# 3_Latch-Connector_Stage.net
KiCad netlist of a schematic drawn in Altium Designer
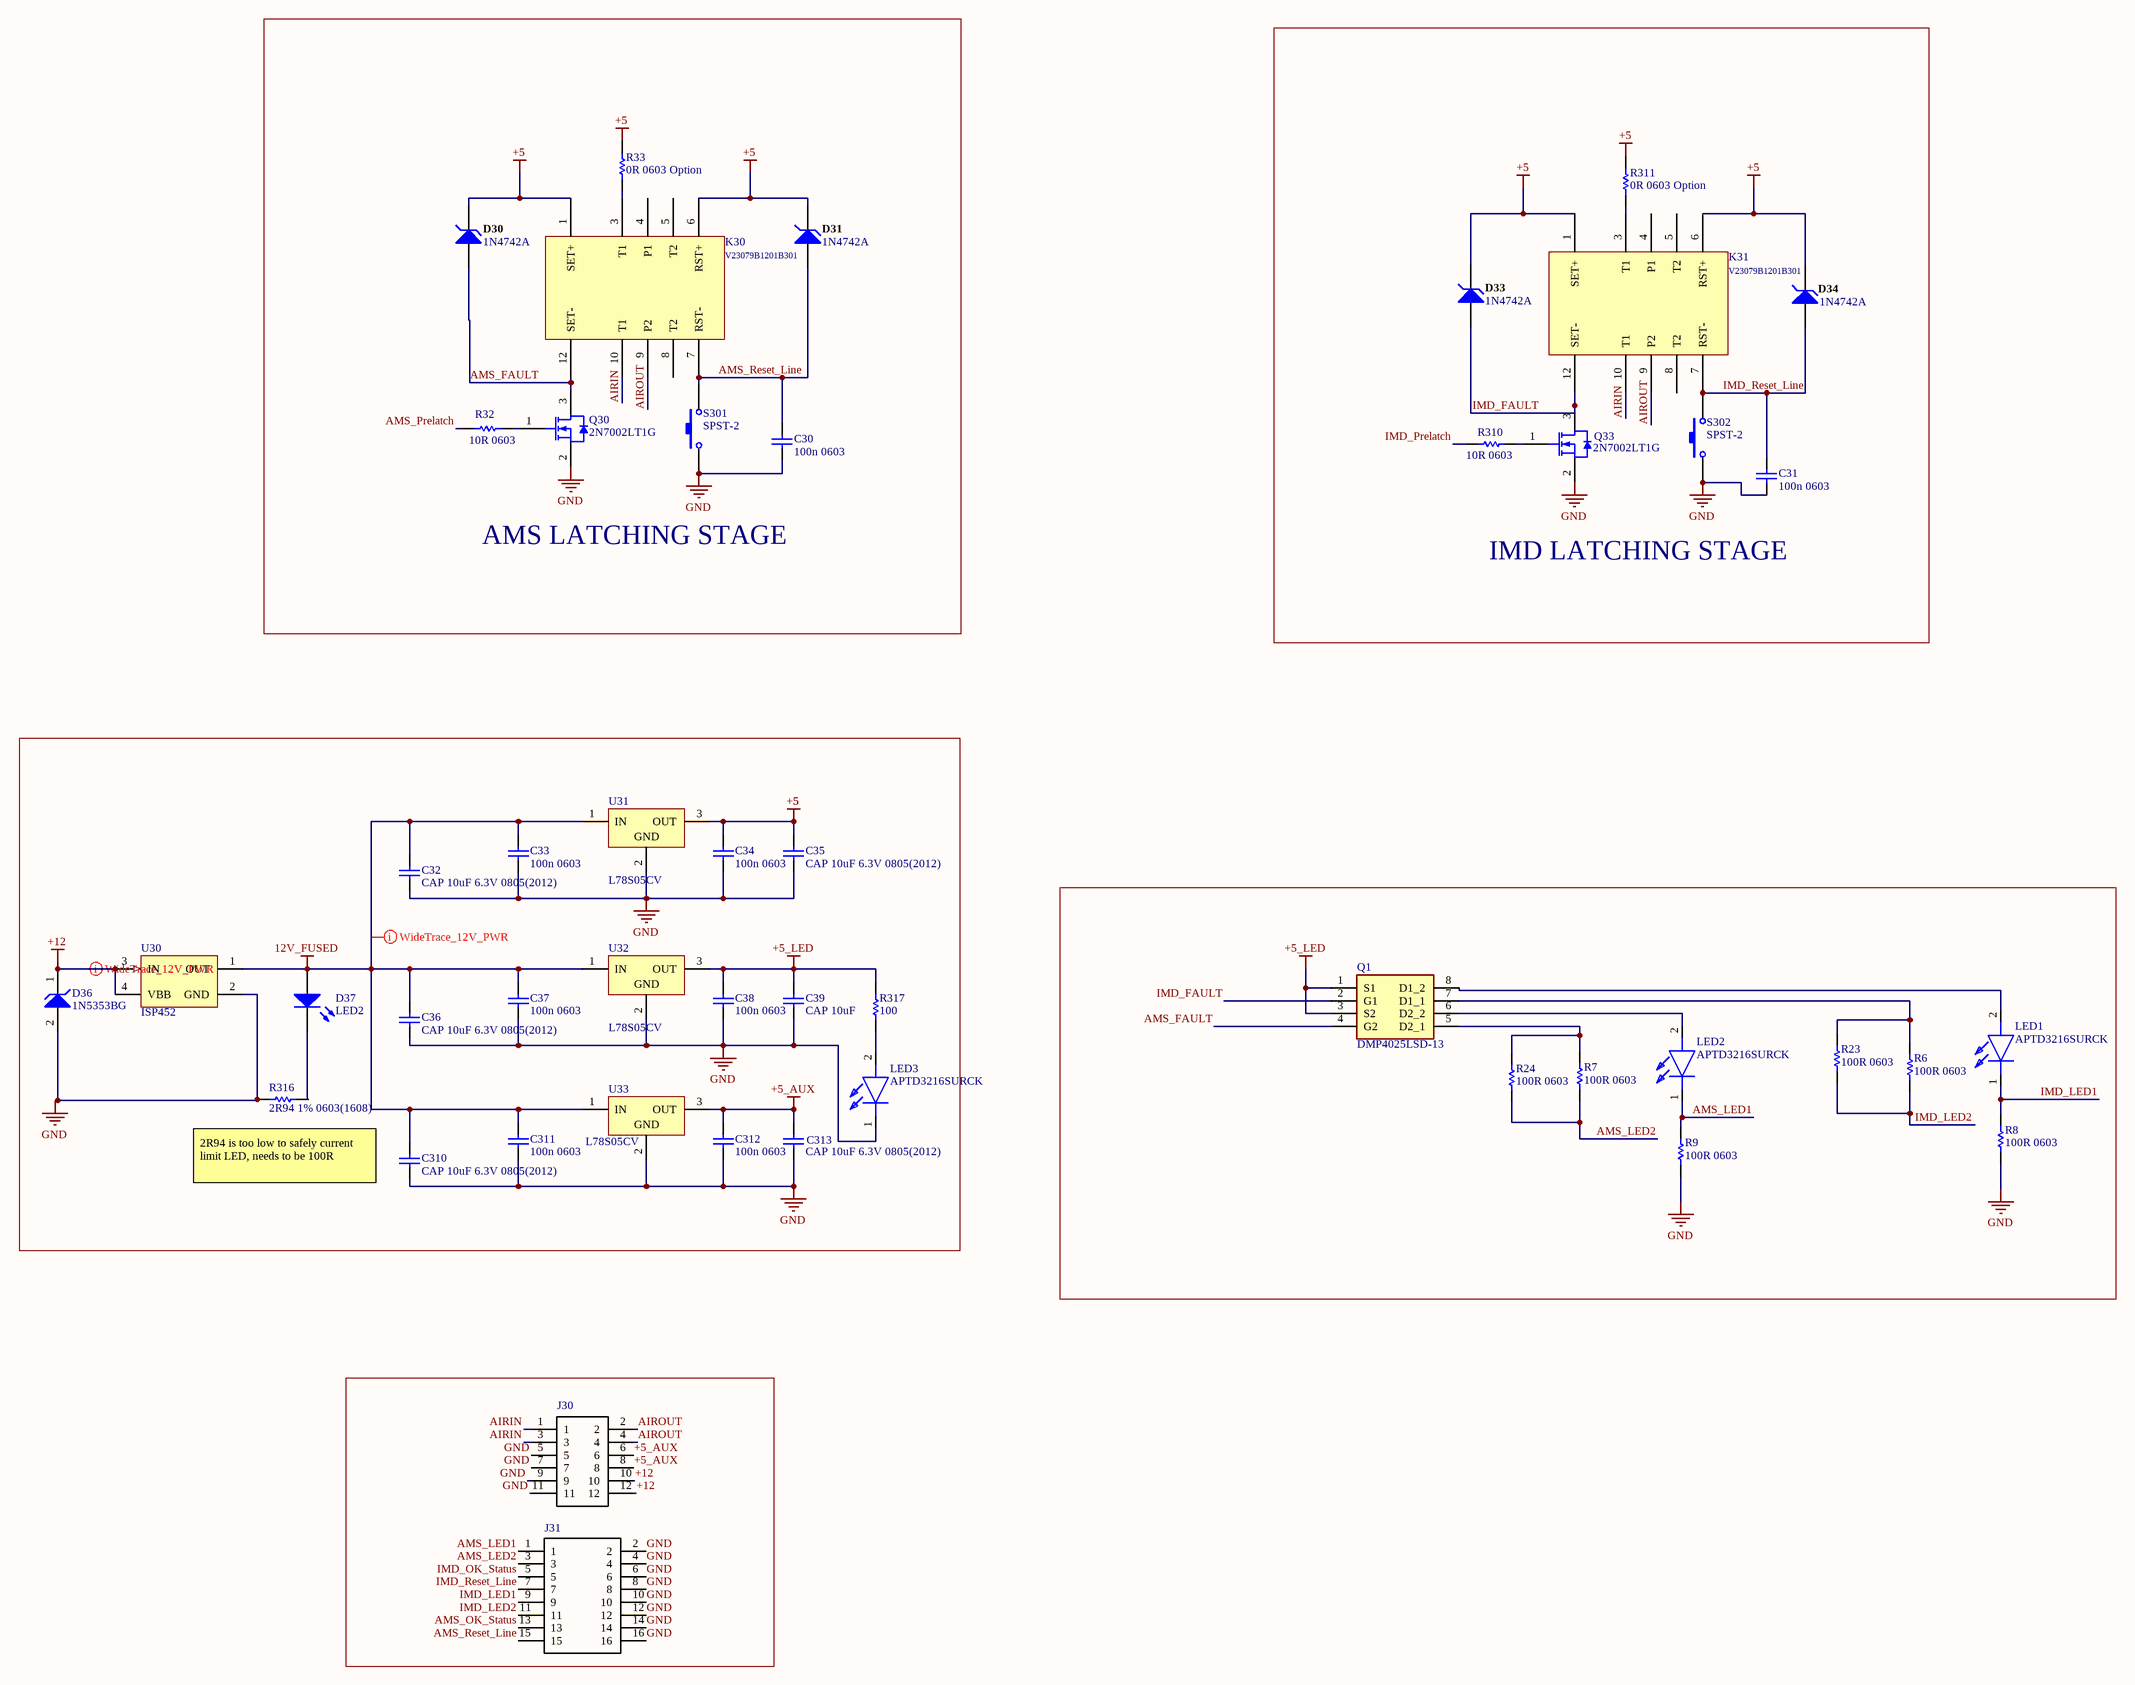
[diagram p0: [3] Latch-Connector_Stage.SchDoc]

(export (version "E")
  (design (tool "Eeschema 10.0.6"))
  (components
    (comp (ref "C30")
      (value "100n 0603")
      (footprint "CAPC0603(1608)100_M")
      (libsource (lib "CAP100n") (part "CAP"))
    )
    (comp (ref "C31")
      (value "100n 0603")
      (footprint "CAPC0603(1608)100_M")
      (libsource (lib "CAP100n") (part "CAP"))
    )
    (comp (ref "C32")
      (value "CAP 10uF 6.3V 0805(2012)")
      (footprint "CAPC0805(2012)145_L")
      (description "CAP 10uF 6.3V ±10% 0805 (2012 Metric) Thickness 1.45mm SMD")
      (fields (field (name "TOLERANCE") "Â±10%"))
      (libsource (lib "Altium Content Vault") (part "CAP"))
    )
    (comp (ref "C33")
      (value "100n 0603")
      (footprint "CAPC0603(1608)100_M")
      (libsource (lib "CAP100n") (part "CAP"))
    )
    (comp (ref "C34")
      (value "100n 0603")
      (footprint "CAPC0603(1608)100_M")
      (libsource (lib "CAP100n") (part "CAP"))
    )
    (comp (ref "C35")
      (value "CAP 10uF 6.3V 0805(2012)")
      (footprint "CAPC0805(2012)145_L")
      (description "CAP 10uF 6.3V ±10% 0805 (2012 Metric) Thickness 1.45mm SMD")
      (fields (field (name "TOLERANCE") "Â±10%"))
      (libsource (lib "Altium Content Vault") (part "CAP"))
    )
    (comp (ref "C36")
      (value "CAP 10uF 6.3V 0805(2012)")
      (footprint "CAPC0805(2012)145_L")
      (description "CAP 10uF 6.3V ±10% 0805 (2012 Metric) Thickness 1.45mm SMD")
      (fields (field (name "TOLERANCE") "Â±10%"))
      (libsource (lib "Altium Content Vault") (part "CAP"))
    )
    (comp (ref "C37")
      (value "100n 0603")
      (footprint "CAPC0603(1608)100_M")
      (libsource (lib "CAP100n") (part "CAP"))
    )
    (comp (ref "C38")
      (value "100n 0603")
      (footprint "CAPC0603(1608)100_M")
      (libsource (lib "CAP100n") (part "CAP"))
    )
    (comp (ref "C39")
      (value "CAP 10uF")
      (footprint "CAPC0805(2012)145_L")
      (description "CAP 10uF 6.3V ±10% 0805 (2012 Metric) Thickness 1.45mm SMD")
      (fields (field (name "TOLERANCE") "Â±10%"))
      (libsource (lib "Altium Content Vault") (part "CAP"))
    )
    (comp (ref "C310")
      (value "CAP 10uF 6.3V 0805(2012)")
      (footprint "CAPC0805(2012)145_L")
      (description "CAP 10uF 6.3V ±10% 0805 (2012 Metric) Thickness 1.45mm SMD")
      (fields (field (name "TOLERANCE") "Â±10%"))
      (libsource (lib "Altium Content Vault") (part "CAP"))
    )
    (comp (ref "C311")
      (value "100n 0603")
      (footprint "CAPC0603(1608)100_M")
      (libsource (lib "CAP100n") (part "CAP"))
    )
    (comp (ref "C312")
      (value "100n 0603")
      (footprint "CAPC0603(1608)100_M")
      (libsource (lib "CAP100n") (part "CAP"))
    )
    (comp (ref "C313")
      (value "CAP 10uF 6.3V 0805(2012)")
      (footprint "CAPC0805(2012)145_L")
      (description "CAP 10uF 6.3V ±10% 0805 (2012 Metric) Thickness 1.45mm SMD")
      (fields (field (name "TOLERANCE") "Â±10%"))
      (libsource (lib "Altium Content Vault") (part "CAP"))
    )
    (comp (ref "D30")
      (value "1N4742A")
      (footprint "FAIR-DO-41-2_V")
      (description "Zener Diode, 12V, 1W, 5%, -65 to 200 degC, 2-Pin DO-41, Body 2.72 x 5.2 mm, RoHS")
      (fields (field (name "TOLERANCE") "5%") (field (name "MANUFACTURER") "Fairchild Semiconductor"))
      (libsource (lib "Altium Content Vault") (part "FAIR-DZEN-A1K2-2"))
    )
    (comp (ref "D31")
      (value "1N4742A")
      (footprint "FAIR-DO-41-2_V")
      (description "Zener Diode, 12V, 1W, 5%, -65 to 200 degC, 2-Pin DO-41, Body 2.72 x 5.2 mm, RoHS")
      (fields (field (name "TOLERANCE") "5%") (field (name "MANUFACTURER") "Fairchild Semiconductor"))
      (libsource (lib "Altium Content Vault") (part "FAIR-DZEN-A1K2-2"))
    )
    (comp (ref "D33")
      (value "1N4742A")
      (footprint "FAIR-DO-41-2_V")
      (description "Zener Diode, 12V, 1W, 5%, -65 to 200 degC, 2-Pin DO-41, Body 2.72 x 5.2 mm, RoHS")
      (fields (field (name "TOLERANCE") "5%") (field (name "MANUFACTURER") "Fairchild Semiconductor"))
      (libsource (lib "Altium Content Vault") (part "FAIR-DZEN-A1K2-2"))
    )
    (comp (ref "D34")
      (value "1N4742A")
      (footprint "FAIR-DO-41-2_V")
      (description "Zener Diode, 12V, 1W, 5%, -65 to 200 degC, 2-Pin DO-41, Body 2.72 x 5.2 mm, RoHS")
      (fields (field (name "TOLERANCE") "5%") (field (name "MANUFACTURER") "Fairchild Semiconductor"))
      (libsource (lib "Altium Content Vault") (part "FAIR-DZEN-A1K2-2"))
    )
    (comp (ref "D36")
      (value "1N5353BG")
      (footprint "ONSC-SURMETIC40-2-017AA-01")
      (description "5 W Zener Voltage Regulator, 2-Pin Surmetic(TM) 40, Pb-Free, Bulk Box")
      (fields (field (name "MANUFACTURER") "On Semiconductor"))
      (libsource (lib "Altium Content Vault") (part "ONSC-K1A2-2"))
    )
    (comp (ref "D37")
      (value "LED2")
      (footprint "3.2X1.6X1.1")
      (description "Typical RED, GREEN, YELLOW, AMBER GaAs LED")
      (fields (field (name "PUBLISHER") "Altium Limited"))
      (libsource (lib "Miscellaneous Devices") (part "LED2"))
    )
    (comp (ref "J30")
      (value "4-794618-2")
      (footprint "*TE_4-794618-2")
      (description "Wire-To-Board Connector, Micro Mate-N-Lok Series, Through Hole, Header, 12, 3 Mm")
      (fields (field (name "MF") "TE Connectivity"))
      (libsource (lib "4-794618-2") (part "4-794618-2"))
    )
    (comp (ref "J31")
      (value "4-794618-6")
      (footprint "*TE_4-794618-6")
      (description "Wire-To-Board Connector, Right Angle, Micro Mate-N-Lok Series, Through Hole, Header, 16, 3 Mm")
      (fields (field (name "MF") "TE Connectivity"))
      (libsource (lib "4-794618-6") (part "4-794618-6"))
    )
    (comp (ref "K30")
      (value "V23079B1201B301")
      (footprint "V23079B1201B301 DPDT")
      (description "V23079B1201B301 DPDT")
      (libsource (lib "V23079B1201B301_Lib") (part "V23079B1201B301"))
    )
    (comp (ref "K31")
      (value "V23079B1201B301")
      (footprint "V23079B1201B301 DPDT")
      (description "V23079B1201B301 DPDT")
      (libsource (lib "V23079B1201B301_Lib") (part "V23079B1201B301"))
    )
    (comp (ref "LED1")
      (value "APTD3216SURCK")
      (footprint "SamacSys:LEDC3216X200N")
      (description "LED")
      (fields (field (name "MOUSER PART NUMBER") "604-APTD-3216SURCK"))
      (libsource (lib "*") (part "APTD3216SURCK"))
    )
    (comp (ref "LED2")
      (value "APTD3216SURCK")
      (footprint "SamacSys:LEDC3216X200N")
      (description "LED")
      (fields (field (name "MOUSER PART NUMBER") "604-APTD-3216SURCK"))
      (libsource (lib "*") (part "APTD3216SURCK"))
    )
    (comp (ref "LED3")
      (value "APTD3216SURCK")
      (footprint "SamacSys:LEDC3216X200N")
      (description "LED")
      (fields (field (name "MOUSER PART NUMBER") "604-APTD-3216SURCK"))
      (libsource (lib "*") (part "APTD3216SURCK"))
    )
    (comp (ref "Q1")
      (value "DMP4025LSD-13")
      (footprint "SamacSys:SOIC127P600X175-8N")
      (description "MOSFET (P-Channel)")
      (fields (field (name "MOUSER PART NUMBER") "621-DMP4025LSD-13"))
      (libsource (lib "*") (part "DMP4025LSD-13"))
    )
    (comp (ref "Q30")
      (value "2N7002LT1G")
      (footprint "ONSC-SOT-23-3-318-08_V")
      (description "Small Signal MOSFET, 60 V, 115 mA, N-Channel, 3-Pin SOT-23, Pb-Free, Tape and Reel")
      (fields (field (name "MANUFACTURER") "On Semiconductor"))
      (libsource (lib "Altium Content Vault") (part "ONSC-NMOS-G1S2D3-3"))
    )
    (comp (ref "Q33")
      (value "2N7002LT1G")
      (footprint "ONSC-SOT-23-3-318-08_V")
      (description "Small Signal MOSFET, 60 V, 115 mA, N-Channel, 3-Pin SOT-23, Pb-Free, Tape and Reel")
      (fields (field (name "MANUFACTURER") "On Semiconductor"))
      (libsource (lib "Altium Content Vault") (part "ONSC-NMOS-G1S2D3-3"))
    )
    (comp (ref "R6")
      (value "100R 0603")
      (footprint "RESC1609X50X30ML8T20")
      (description "Chip Resistor, 100 Ohm, +/- 1%, 100 mW,-55 to 155 degC, 0603 (1608 Metric), RoHS, Tape and Ree")
      (fields (field (name "MANUFACTURER") "Vishay Semiconductor"))
      (libsource (lib "Altium Content Vault") (part "RES-2"))
    )
    (comp (ref "R7")
      (value "100R 0603")
      (footprint "RESC1609X50X30ML8T20")
      (description "Chip Resistor, 100 Ohm, +/- 1%, 100 mW,-55 to 155 degC, 0603 (1608 Metric), RoHS, Tape and Ree")
      (fields (field (name "MANUFACTURER") "Vishay Semiconductor"))
      (libsource (lib "Altium Content Vault") (part "RES-2"))
    )
    (comp (ref "R8")
      (value "100R 0603")
      (footprint "RESC1609X50X30ML8T20")
      (description "Chip Resistor, 100 Ohm, +/- 1%, 100 mW,-55 to 155 degC, 0603 (1608 Metric), RoHS, Tape and Ree")
      (fields (field (name "MANUFACTURER") "Vishay Semiconductor"))
      (libsource (lib "Altium Content Vault") (part "RES-2"))
    )
    (comp (ref "R9")
      (value "100R 0603")
      (footprint "RESC1609X50X30ML8T20")
      (description "Chip Resistor, 100 Ohm, +/- 1%, 100 mW,-55 to 155 degC, 0603 (1608 Metric), RoHS, Tape and Ree")
      (fields (field (name "MANUFACTURER") "Vishay Semiconductor"))
      (libsource (lib "Altium Content Vault") (part "RES-2"))
    )
    (comp (ref "R23")
      (value "100R 0603")
      (footprint "RESC1609X50X30ML8T20")
      (description "Chip Resistor, 100 Ohm, +/- 1%, 100 mW,-55 to 155 degC, 0603 (1608 Metric), RoHS, Tape and Ree")
      (fields (field (name "MANUFACTURER") "Vishay Semiconductor"))
      (libsource (lib "Altium Content Vault") (part "RES-2"))
    )
    (comp (ref "R24")
      (value "100R 0603")
      (footprint "RESC1609X50X30ML8T20")
      (description "Chip Resistor, 100 Ohm, +/- 1%, 100 mW,-55 to 155 degC, 0603 (1608 Metric), RoHS, Tape and Ree")
      (fields (field (name "MANUFACTURER") "Vishay Semiconductor"))
      (libsource (lib "Altium Content Vault") (part "RES-2"))
    )
    (comp (ref "R32")
      (value "10R 0603")
      (footprint "CAPC0603(1608)100_M")
      (description "Resistor")
      (fields (field (name "PUBLISHER") "Altium Limited"))
      (libsource (lib "Miscellaneous Devices") (part "Res1"))
    )
    (comp (ref "R33")
      (value "0R 0603 Option")
      (footprint "CAPC0603(1608)100_M")
      (libsource (lib "RES100k") (part "RES"))
    )
    (comp (ref "R310")
      (value "10R 0603")
      (footprint "CAPC0603(1608)100_M")
      (description "Resistor")
      (fields (field (name "PUBLISHER") "Altium Limited"))
      (libsource (lib "Miscellaneous Devices") (part "Res1"))
    )
    (comp (ref "R311")
      (value "0R 0603 Option")
      (footprint "CAPC0603(1608)100_M")
      (libsource (lib "RES100k") (part "RES"))
    )
    (comp (ref "R316")
      (value "2R94 1% 0603(1608)")
      (footprint "RESC0603(1608)_L")
      (description "2R94 0.1W 1% 0603 (1608 Metric)  SMD")
      (fields (field (name "POWER") "0.1 W") (field (name "TOLERANCE") "1 %"))
      (libsource (lib "Altium Content Vault") (part "RES"))
    )
    (comp (ref "R317")
      (value "100")
      (footprint "RESC0603(1608)_L")
      (description "2R94 0.1W 1% 0603 (1608 Metric)  SMD")
      (fields (field (name "POWER") "0.1 W") (field (name "TOLERANCE") "1 %"))
      (libsource (lib "Altium Content Vault") (part "RES"))
    )
    (comp (ref "S301")
      (value "SPST-2")
      (footprint "SPST-2")
      (description "Switch")
      (fields (field (name "PUBLISHER") "Altium Limited"))
      (libsource (lib "Miscellaneous Devices") (part "SW-PB"))
    )
    (comp (ref "S302")
      (value "SPST-2")
      (footprint "SPST-2")
      (description "Switch")
      (fields (field (name "PUBLISHER") "Altium Limited"))
      (libsource (lib "Miscellaneous Devices") (part "SW-PB"))
    )
    (comp (ref "U30")
      (value "ISP452")
      (footprint "INF-SOT223_L")
      (fields (field (name "MANUFACTURER") "Infineon"))
      (libsource (lib "Altium Content Vault") (part "INF-ISP452-SOT223-4"))
    )
    (comp (ref "U31")
      (value "L78S05CV")
      (footprint "TO220")
      (description "2A Positive Voltage Regulator, 5V, 3-Pin TO-220")
      (libsource (lib "Altium Content Vault") (part "PM-REG-L4940-SIL3"))
    )
    (comp (ref "U32")
      (value "L78S05CV")
      (footprint "TO220")
      (description "2A Positive Voltage Regulator, 5V, 3-Pin TO-220")
      (libsource (lib "Altium Content Vault") (part "PM-REG-L4940-SIL3"))
    )
    (comp (ref "U33")
      (value "L78S05CV")
      (footprint "TO220")
      (description "2A Positive Voltage Regulator, 5V, 3-Pin TO-220")
      (libsource (lib "Altium Content Vault") (part "PM-REG-L4940-SIL3"))
    )
  )
  (nets
    (net (code "1") (name "+5") (class "Default")
      (node (ref "C34") (pin "2") (pinfunction "2_2") (pintype "passive"))
      (node (ref "C35") (pin "2") (pinfunction "2_2") (pintype "passive"))
      (node (ref "D30") (pin "2") (pinfunction "K_2") (pintype "passive"))
      (node (ref "D31") (pin "2") (pinfunction "K_2") (pintype "passive"))
      (node (ref "D33") (pin "2") (pinfunction "K_2") (pintype "passive"))
      (node (ref "D34") (pin "2") (pinfunction "K_2") (pintype "passive"))
      (node (ref "K30") (pin "1") (pinfunction "SET+_1") (pintype "passive"))
      (node (ref "K30") (pin "6") (pinfunction "RST+_6") (pintype "passive"))
      (node (ref "K31") (pin "1") (pinfunction "SET+_1") (pintype "passive"))
      (node (ref "K31") (pin "6") (pinfunction "RST+_6") (pintype "passive"))
      (node (ref "R311") (pin "2") (pinfunction "2_2") (pintype "passive"))
      (node (ref "R33") (pin "2") (pinfunction "2_2") (pintype "passive"))
      (node (ref "U31") (pin "3") (pinfunction "OUT_3") (pintype "power_in"))
    )
    (net (code "2") (name "+5_AUX") (class "Default")
      (node (ref "C312") (pin "2") (pinfunction "2_2") (pintype "passive"))
      (node (ref "C313") (pin "2") (pinfunction "2_2") (pintype "passive"))
      (node (ref "J30") (pin "6") (pinfunction "6_6") (pintype "passive"))
      (node (ref "J30") (pin "8") (pinfunction "8_8") (pintype "passive"))
      (node (ref "U33") (pin "3") (pinfunction "OUT_3") (pintype "power_in"))
    )
    (net (code "3") (name "+5_LED") (class "Default")
      (node (ref "C38") (pin "2") (pinfunction "2_2") (pintype "passive"))
      (node (ref "C39") (pin "2") (pinfunction "2_2") (pintype "passive"))
      (node (ref "Q1") (pin "1") (pinfunction "S1_1") (pintype "passive"))
      (node (ref "Q1") (pin "3") (pinfunction "S2_3") (pintype "passive"))
      (node (ref "R317") (pin "2") (pinfunction "2_2") (pintype "passive"))
      (node (ref "U32") (pin "3") (pinfunction "OUT_3") (pintype "power_in"))
    )
    (net (code "4") (name "+12") (class "Default")
      (node (ref "D36") (pin "1") (pinfunction "K_1") (pintype "passive"))
      (node (ref "J30") (pin "10") (pinfunction "10_10") (pintype "passive"))
      (node (ref "J30") (pin "12") (pinfunction "12_12") (pintype "passive"))
      (node (ref "U30") (pin "3") (pinfunction "IN_3") (pintype "input"))
      (node (ref "U30") (pin "4") (pinfunction "VBB_4") (pintype "power_in"))
    )
    (net (code "5") (name "/AIRIN") (class "Default")
      (node (ref "J30") (pin "1") (pinfunction "1_1") (pintype "passive"))
      (node (ref "J30") (pin "3") (pinfunction "3_3") (pintype "passive"))
      (node (ref "K30") (pin "10") (pinfunction "T1_10") (pintype "passive"))
      (node (ref "K31") (pin "10") (pinfunction "T1_10") (pintype "passive"))
    )
    (net (code "6") (name "/AIROUT") (class "Default")
      (node (ref "J30") (pin "2") (pinfunction "2_2") (pintype "passive"))
      (node (ref "J30") (pin "4") (pinfunction "4_4") (pintype "passive"))
      (node (ref "K30") (pin "9") (pinfunction "P2_9") (pintype "passive"))
      (node (ref "K31") (pin "9") (pinfunction "P2_9") (pintype "passive"))
    )
    (net (code "7") (name "/AMS_FAULT") (class "Default")
      (node (ref "D30") (pin "1") (pinfunction "A_1") (pintype "passive"))
      (node (ref "K30") (pin "12") (pinfunction "SET-_12") (pintype "passive"))
      (node (ref "Q1") (pin "4") (pinfunction "G2_4") (pintype "passive"))
      (node (ref "Q30") (pin "3") (pinfunction "D_3") (pintype "passive"))
    )
    (net (code "8") (name "/AMS_LED1") (class "Default")
      (node (ref "J31") (pin "1") (pinfunction "1_1") (pintype "passive"))
      (node (ref "LED2") (pin "1") (pinfunction "K_1") (pintype "passive"))
      (node (ref "R9") (pin "2") (pinfunction "2_2") (pintype "passive"))
    )
    (net (code "9") (name "/AMS_LED2") (class "Default")
      (node (ref "J31") (pin "3") (pinfunction "3_3") (pintype "passive"))
      (node (ref "R24") (pin "1") (pinfunction "1_1") (pintype "passive"))
      (node (ref "R7") (pin "1") (pinfunction "1_1") (pintype "passive"))
    )
    (net (code "10") (name "/AMS_OK_Status") (class "Default")
      (node (ref "J31") (pin "13") (pinfunction "13_13") (pintype "passive"))
    )
    (net (code "11") (name "/AMS_Prelatch") (class "Default")
      (node (ref "R32") (pin "1") (pinfunction "1_1") (pintype "passive"))
    )
    (net (code "12") (name "/AMS_Reset_Line") (class "Default")
      (node (ref "C30") (pin "2") (pinfunction "2_2") (pintype "passive"))
      (node (ref "D31") (pin "1") (pinfunction "A_1") (pintype "passive"))
      (node (ref "J31") (pin "15") (pinfunction "15_15") (pintype "passive"))
      (node (ref "K30") (pin "7") (pinfunction "RST-_7") (pintype "passive"))
      (node (ref "S301") (pin "2") (pinfunction "2_2") (pintype "passive"))
    )
    (net (code "13") (name "/IMD_FAULT") (class "Default")
      (node (ref "D33") (pin "1") (pinfunction "A_1") (pintype "passive"))
      (node (ref "K31") (pin "12") (pinfunction "SET-_12") (pintype "passive"))
      (node (ref "Q1") (pin "2") (pinfunction "G1_2") (pintype "passive"))
      (node (ref "Q33") (pin "3") (pinfunction "D_3") (pintype "passive"))
    )
    (net (code "14") (name "/IMD_LED1") (class "Default")
      (node (ref "J31") (pin "9") (pinfunction "9_9") (pintype "passive"))
      (node (ref "LED1") (pin "1") (pinfunction "K_1") (pintype "passive"))
      (node (ref "R8") (pin "2") (pinfunction "2_2") (pintype "passive"))
    )
    (net (code "15") (name "/IMD_LED2") (class "Default")
      (node (ref "J31") (pin "11") (pinfunction "11_11") (pintype "passive"))
      (node (ref "R23") (pin "1") (pinfunction "1_1") (pintype "passive"))
      (node (ref "R6") (pin "1") (pinfunction "1_1") (pintype "passive"))
    )
    (net (code "16") (name "/IMD_OK_Status") (class "Default")
      (node (ref "J31") (pin "5") (pinfunction "5_5") (pintype "passive"))
    )
    (net (code "17") (name "/IMD_Prelatch") (class "Default")
      (node (ref "R310") (pin "1") (pinfunction "1_1") (pintype "passive"))
    )
    (net (code "18") (name "/IMD_Reset_Line") (class "Default")
      (node (ref "C31") (pin "2") (pinfunction "2_2") (pintype "passive"))
      (node (ref "D34") (pin "1") (pinfunction "A_1") (pintype "passive"))
      (node (ref "J31") (pin "7") (pinfunction "7_7") (pintype "passive"))
      (node (ref "K31") (pin "7") (pinfunction "RST-_7") (pintype "passive"))
      (node (ref "S302") (pin "2") (pinfunction "2_2") (pintype "passive"))
    )
    (net (code "19") (name "12V_FUSED") (class "Default")
      (node (ref "C310") (pin "2") (pinfunction "2_2") (pintype "passive"))
      (node (ref "C311") (pin "2") (pinfunction "2_2") (pintype "passive"))
      (node (ref "C32") (pin "2") (pinfunction "2_2") (pintype "passive"))
      (node (ref "C33") (pin "2") (pinfunction "2_2") (pintype "passive"))
      (node (ref "C36") (pin "2") (pinfunction "2_2") (pintype "passive"))
      (node (ref "C37") (pin "2") (pinfunction "2_2") (pintype "passive"))
      (node (ref "D37") (pin "1") (pinfunction "A_1") (pintype "passive"))
      (node (ref "U30") (pin "1") (pinfunction "OUT_1") (pintype "power_in"))
      (node (ref "U31") (pin "1") (pinfunction "IN_1") (pintype "power_in"))
      (node (ref "U32") (pin "1") (pinfunction "IN_1") (pintype "power_in"))
      (node (ref "U33") (pin "1") (pinfunction "IN_1") (pintype "power_in"))
    )
    (net (code "20") (name "GND") (class "Default")
      (node (ref "C30") (pin "1") (pinfunction "1_1") (pintype "passive"))
      (node (ref "C31") (pin "1") (pinfunction "1_1") (pintype "passive"))
      (node (ref "C310") (pin "1") (pinfunction "1_1") (pintype "passive"))
      (node (ref "C311") (pin "1") (pinfunction "1_1") (pintype "passive"))
      (node (ref "C312") (pin "1") (pinfunction "1_1") (pintype "passive"))
      (node (ref "C313") (pin "1") (pinfunction "1_1") (pintype "passive"))
      (node (ref "C32") (pin "1") (pinfunction "1_1") (pintype "passive"))
      (node (ref "C33") (pin "1") (pinfunction "1_1") (pintype "passive"))
      (node (ref "C34") (pin "1") (pinfunction "1_1") (pintype "passive"))
      (node (ref "C35") (pin "1") (pinfunction "1_1") (pintype "passive"))
      (node (ref "C36") (pin "1") (pinfunction "1_1") (pintype "passive"))
      (node (ref "C37") (pin "1") (pinfunction "1_1") (pintype "passive"))
      (node (ref "C38") (pin "1") (pinfunction "1_1") (pintype "passive"))
      (node (ref "C39") (pin "1") (pinfunction "1_1") (pintype "passive"))
      (node (ref "D36") (pin "2") (pinfunction "A_2") (pintype "passive"))
      (node (ref "J30") (pin "11") (pinfunction "11_11") (pintype "passive"))
      (node (ref "J30") (pin "5") (pinfunction "5_5") (pintype "passive"))
      (node (ref "J30") (pin "7") (pinfunction "7_7") (pintype "passive"))
      (node (ref "J30") (pin "9") (pinfunction "9_9") (pintype "passive"))
      (node (ref "J31") (pin "10") (pinfunction "10_10") (pintype "passive"))
      (node (ref "J31") (pin "12") (pinfunction "12_12") (pintype "passive"))
      (node (ref "J31") (pin "14") (pinfunction "14_14") (pintype "passive"))
      (node (ref "J31") (pin "16") (pinfunction "16_16") (pintype "passive"))
      (node (ref "J31") (pin "2") (pinfunction "2_2") (pintype "passive"))
      (node (ref "J31") (pin "4") (pinfunction "4_4") (pintype "passive"))
      (node (ref "J31") (pin "6") (pinfunction "6_6") (pintype "passive"))
      (node (ref "J31") (pin "8") (pinfunction "8_8") (pintype "passive"))
      (node (ref "LED3") (pin "1") (pinfunction "K_1") (pintype "passive"))
      (node (ref "Q30") (pin "2") (pinfunction "S_2") (pintype "passive"))
      (node (ref "Q33") (pin "2") (pinfunction "S_2") (pintype "passive"))
      (node (ref "R316") (pin "1") (pinfunction "1_1") (pintype "passive"))
      (node (ref "R8") (pin "1") (pinfunction "1_1") (pintype "passive"))
      (node (ref "R9") (pin "1") (pinfunction "1_1") (pintype "passive"))
      (node (ref "S301") (pin "1") (pinfunction "1_1") (pintype "passive"))
      (node (ref "S302") (pin "1") (pinfunction "1_1") (pintype "passive"))
      (node (ref "U30") (pin "2") (pinfunction "GND_2") (pintype "power_in"))
      (node (ref "U31") (pin "2") (pinfunction "GND_2") (pintype "power_in"))
      (node (ref "U32") (pin "2") (pinfunction "GND_2") (pintype "power_in"))
      (node (ref "U33") (pin "2") (pinfunction "GND_2") (pintype "power_in"))
    )
    (net (code "21") (name "Net-(D37-K)") (class "Default")
      (node (ref "D37") (pin "2") (pinfunction "K_2") (pintype "passive"))
      (node (ref "R316") (pin "2") (pinfunction "2_2") (pintype "passive"))
    )
    (net (code "22") (name "Net-(K30-T1-Pad3)") (class "Default")
      (node (ref "K30") (pin "3") (pinfunction "T1_3") (pintype "passive"))
      (node (ref "R33") (pin "1") (pinfunction "1_1") (pintype "passive"))
    )
    (net (code "23") (name "Net-(K31-T1-Pad3)") (class "Default")
      (node (ref "K31") (pin "3") (pinfunction "T1_3") (pintype "passive"))
      (node (ref "R311") (pin "1") (pinfunction "1_1") (pintype "passive"))
    )
    (net (code "24") (name "Net-(LED1-A)") (class "Default")
      (node (ref "LED1") (pin "2") (pinfunction "A_2") (pintype "passive"))
      (node (ref "Q1") (pin "8") (pinfunction "D1_2_8") (pintype "passive"))
    )
    (net (code "25") (name "Net-(LED2-A)") (class "Default")
      (node (ref "LED2") (pin "2") (pinfunction "A_2") (pintype "passive"))
      (node (ref "Q1") (pin "6") (pinfunction "D2_2_6") (pintype "passive"))
    )
    (net (code "26") (name "Net-(LED3-A)") (class "Default")
      (node (ref "LED3") (pin "2") (pinfunction "A_2") (pintype "passive"))
      (node (ref "R317") (pin "1") (pinfunction "1_1") (pintype "passive"))
    )
    (net (code "27") (name "Net-(Q1-D1_1)") (class "Default")
      (node (ref "Q1") (pin "7") (pinfunction "D1_1_7") (pintype "passive"))
      (node (ref "R23") (pin "2") (pinfunction "2_2") (pintype "passive"))
      (node (ref "R6") (pin "2") (pinfunction "2_2") (pintype "passive"))
    )
    (net (code "28") (name "Net-(Q1-D2_1)") (class "Default")
      (node (ref "Q1") (pin "5") (pinfunction "D2_1_5") (pintype "passive"))
      (node (ref "R24") (pin "2") (pinfunction "2_2") (pintype "passive"))
      (node (ref "R7") (pin "2") (pinfunction "2_2") (pintype "passive"))
    )
    (net (code "29") (name "Net-(Q30-G)") (class "Default")
      (node (ref "Q30") (pin "1") (pinfunction "G_1") (pintype "passive"))
      (node (ref "R32") (pin "2") (pinfunction "2_2") (pintype "passive"))
    )
    (net (code "30") (name "Net-(Q33-G)") (class "Default")
      (node (ref "Q33") (pin "1") (pinfunction "G_1") (pintype "passive"))
      (node (ref "R310") (pin "2") (pinfunction "2_2") (pintype "passive"))
    )
    (net (code "31") (name "unconnected-(K30-P1-Pad4)") (class "Default")
      (node (ref "K30") (pin "4") (pinfunction "P1_4") (pintype "passive"))
    )
    (net (code "32") (name "unconnected-(K30-T2-Pad5)") (class "Default")
      (node (ref "K30") (pin "5") (pinfunction "T2_5") (pintype "passive"))
    )
    (net (code "33") (name "unconnected-(K30-T2-Pad8)") (class "Default")
      (node (ref "K30") (pin "8") (pinfunction "T2_8") (pintype "passive"))
    )
    (net (code "34") (name "unconnected-(K31-P1-Pad4)") (class "Default")
      (node (ref "K31") (pin "4") (pinfunction "P1_4") (pintype "passive"))
    )
    (net (code "35") (name "unconnected-(K31-T2-Pad5)") (class "Default")
      (node (ref "K31") (pin "5") (pinfunction "T2_5") (pintype "passive"))
    )
    (net (code "36") (name "unconnected-(K31-T2-Pad8)") (class "Default")
      (node (ref "K31") (pin "8") (pinfunction "T2_8") (pintype "passive"))
    )
  )
)
